# PannelInterface.net
KiCad netlist of a schematic drawn in EAGLE
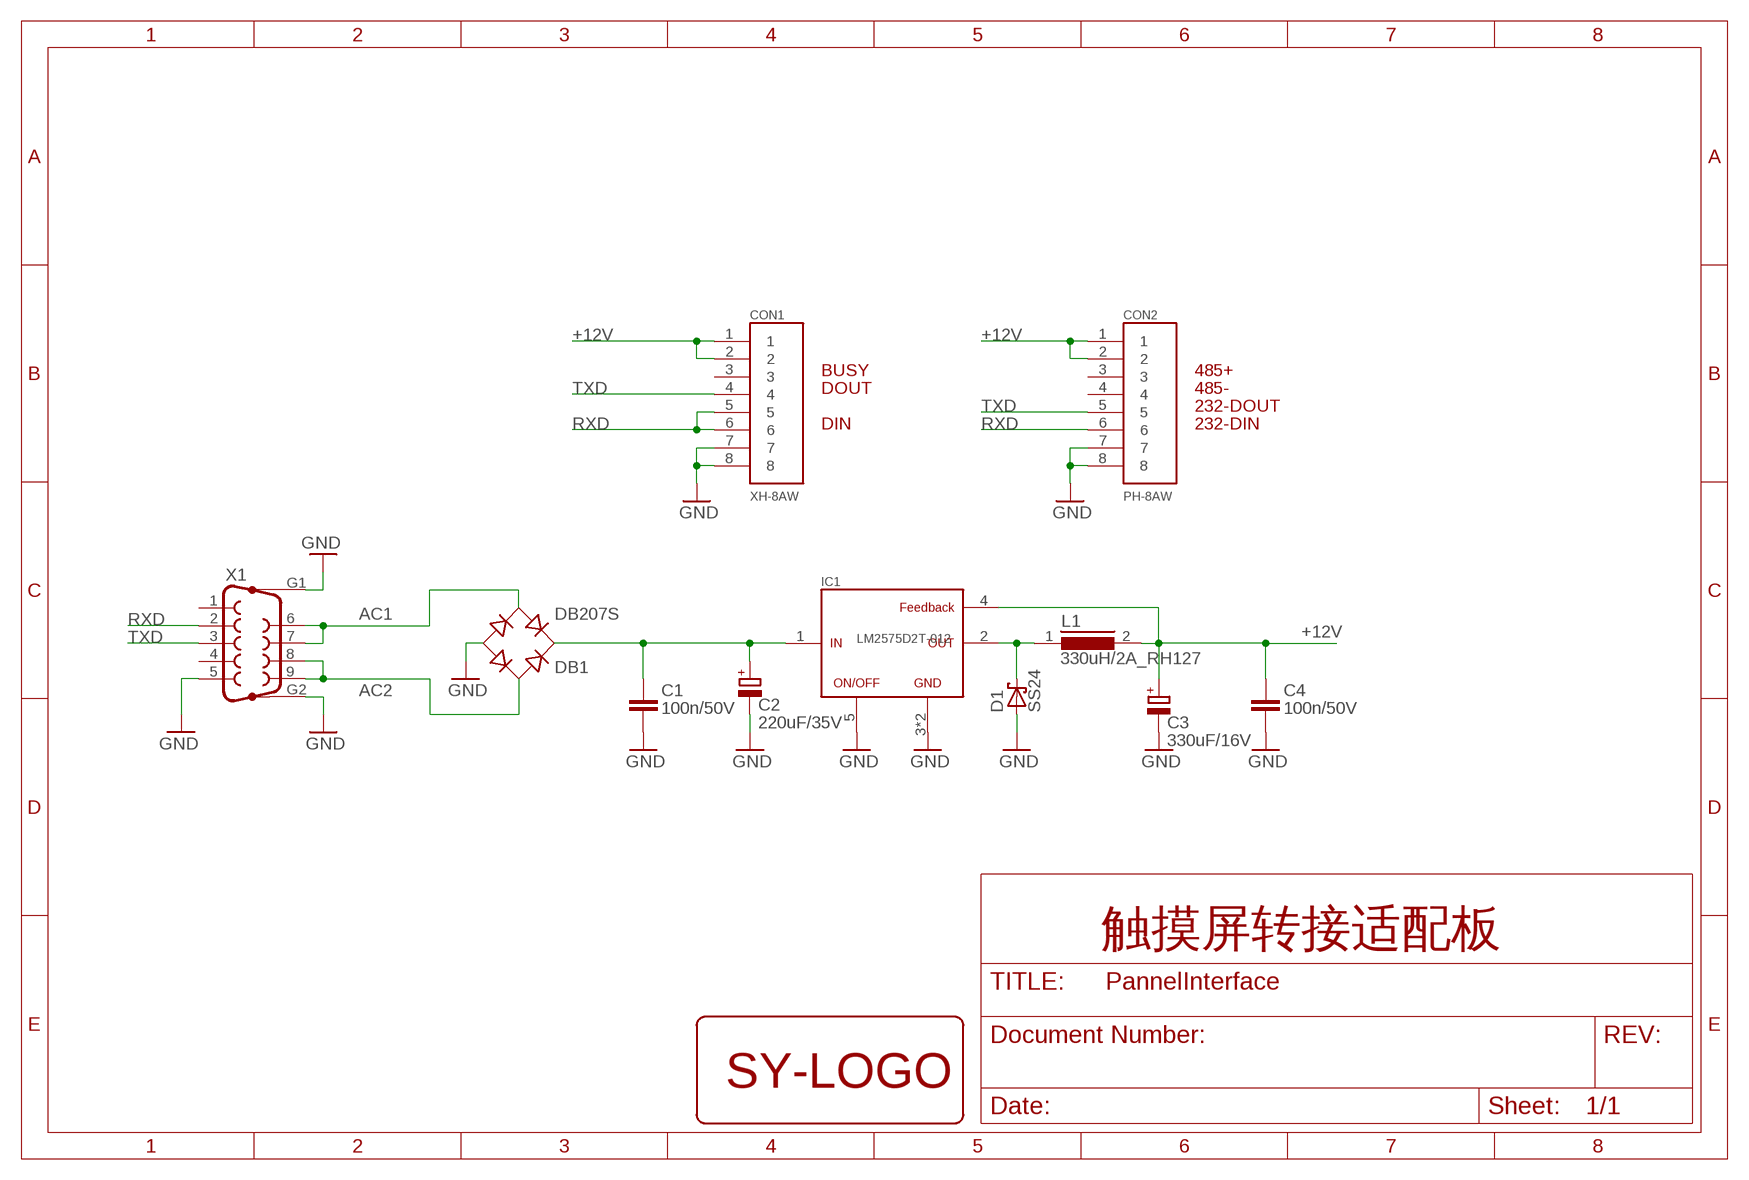
[diagram p0: schematic, sheet 1]

(export (version "E")
  (design (tool "Eeschema 10.0.6"))
  (components
    (comp (ref "C1")
      (value "100n/50V")
      (footprint "eagle-import:C0805")
      (libsource (lib "eagle-import") (part "C0805"))
    )
    (comp (ref "C2")
      (value "220uF/35V")
      (footprint "eagle-import:TT5D11")
      (libsource (lib "eagle-import") (part "CPOL-EUTT5D11"))
    )
    (comp (ref "C3")
      (value "330uF/16V")
      (footprint "eagle-import:UD-8X10_NICHICON")
      (libsource (lib "eagle-import") (part "CPOL-EUUD-8X10"))
    )
    (comp (ref "C4")
      (value "100n/50V")
      (footprint "eagle-import:C0805")
      (libsource (lib "eagle-import") (part "C0805"))
    )
    (comp (ref "CON1")
      (value "XH-8AW")
      (footprint "eagle-import:XH-8AW")
      (libsource (lib "eagle-import") (part "XH-8AW"))
    )
    (comp (ref "CON2")
      (value "PH-8AW")
      (footprint "eagle-import:PH-8AW")
      (libsource (lib "eagle-import") (part "PH-8AW"))
    )
    (comp (ref "D1")
      (value "SS24")
      (footprint "eagle-import:DO214AA")
      (libsource (lib "eagle-import") (part "SCHOTTKY-DIODE-SS24"))
    )
    (comp (ref "DB1")
      (value "DB207S")
      (footprint "eagle-import:DBS")
      (libsource (lib "eagle-import") (part "DB207S"))
    )
    (comp (ref "IC1")
      (value "LM2575D2T-012")
      (footprint "eagle-import:DDPAK-5_MICROCHIP")
      (libsource (lib "eagle-import") (part "LM2575D2T"))
    )
    (comp (ref "L1")
      (value "330uH/2A_RH127")
      (footprint "eagle-import:MSS1260")
      (libsource (lib "eagle-import") (part "POWER_INDUCTOR-1260"))
    )
    (comp (ref "LOGO1")
      (value "SY-LOGO_BOTTOM")
      (footprint "eagle-import:SY-LOGO_BOTTOM")
      (libsource (lib "eagle-import") (part "SY-LOGO_BOTTOM"))
    )
    (comp (ref "X1")
      (value "F09HP")
      (footprint "eagle-import:F09HP")
      (libsource (lib "eagle-import") (part "F09HP"))
    )
  )
  (nets
    (net (code "1") (name "/+12V") (class "Default")
      (node (ref "C3") (pin "+") (pinfunction "+_+") (pintype "passive"))
      (node (ref "C4") (pin "1") (pinfunction "1_1") (pintype "passive"))
      (node (ref "CON1") (pin "1") (pinfunction "1_1") (pintype "passive"))
      (node (ref "CON1") (pin "2") (pinfunction "2_2") (pintype "passive"))
      (node (ref "CON2") (pin "1") (pinfunction "1_1") (pintype "passive"))
      (node (ref "CON2") (pin "2") (pinfunction "2_2") (pintype "passive"))
      (node (ref "IC1") (pin "4") (pinfunction "4_4") (pintype "input"))
      (node (ref "L1") (pin "2") (pinfunction "2_2") (pintype "passive"))
    )
    (net (code "2") (name "/AC1") (class "Default")
      (node (ref "DB1") (pin "AC2") (pinfunction "AC2_AC2") (pintype "passive"))
      (node (ref "X1") (pin "6") (pinfunction "6_6") (pintype "passive"))
      (node (ref "X1") (pin "7") (pinfunction "7_7") (pintype "passive"))
    )
    (net (code "3") (name "/AC2") (class "Default")
      (node (ref "DB1") (pin "AC1") (pinfunction "AC1_AC1") (pintype "passive"))
      (node (ref "X1") (pin "8") (pinfunction "8_8") (pintype "passive"))
      (node (ref "X1") (pin "9") (pinfunction "9_9") (pintype "passive"))
    )
    (net (code "4") (name "/RXD") (class "Default")
      (node (ref "CON1") (pin "5") (pinfunction "5_5") (pintype "passive"))
      (node (ref "CON1") (pin "6") (pinfunction "6_6") (pintype "passive"))
      (node (ref "CON2") (pin "6") (pinfunction "6_6") (pintype "passive"))
      (node (ref "X1") (pin "2") (pinfunction "2_2") (pintype "passive"))
    )
    (net (code "5") (name "/TXD") (class "Default")
      (node (ref "CON1") (pin "4") (pinfunction "4_4") (pintype "passive"))
      (node (ref "CON2") (pin "5") (pinfunction "5_5") (pintype "passive"))
      (node (ref "X1") (pin "3") (pinfunction "3_3") (pintype "passive"))
    )
    (net (code "6") (name "GND") (class "Default")
      (node (ref "C1") (pin "2") (pinfunction "2_2") (pintype "passive"))
      (node (ref "C2") (pin "-") (pinfunction "-_-") (pintype "passive"))
      (node (ref "C3") (pin "-") (pinfunction "-_-") (pintype "passive"))
      (node (ref "C4") (pin "2") (pinfunction "2_2") (pintype "passive"))
      (node (ref "CON1") (pin "7") (pinfunction "7_7") (pintype "passive"))
      (node (ref "CON1") (pin "8") (pinfunction "8_8") (pintype "passive"))
      (node (ref "CON2") (pin "7") (pinfunction "7_7") (pintype "passive"))
      (node (ref "CON2") (pin "8") (pinfunction "8_8") (pintype "passive"))
      (node (ref "D1") (pin "A") (pinfunction "A_A") (pintype "passive"))
      (node (ref "DB1") (pin "-") (pinfunction "-_-") (pintype "passive"))
      (node (ref "IC1") (pin "3") (pinfunction "3_3") (pintype "power_in"))
      (node (ref "IC1") (pin "5") (pinfunction "5_5") (pintype "input"))
      (node (ref "IC1") (pin "6") (pinfunction "3_6") (pintype "power_in"))
      (node (ref "X1") (pin "5") (pinfunction "5_5") (pintype "passive"))
      (node (ref "X1") (pin "G1") (pinfunction "G1_G1") (pintype "passive"))
      (node (ref "X1") (pin "G2") (pinfunction "G2_G2") (pintype "passive"))
    )
    (net (code "7") (name "Net-(C1-Pad1)") (class "Default")
      (node (ref "C1") (pin "1") (pinfunction "1_1") (pintype "passive"))
      (node (ref "C2") (pin "+") (pinfunction "+_+") (pintype "passive"))
      (node (ref "DB1") (pin "+") (pinfunction "+_+") (pintype "passive"))
      (node (ref "IC1") (pin "1") (pinfunction "1_1") (pintype "input"))
    )
    (net (code "8") (name "Net-(D1-PadC)") (class "Default")
      (node (ref "D1") (pin "C") (pinfunction "C_C") (pintype "passive"))
      (node (ref "IC1") (pin "2") (pinfunction "2_2") (pintype "output"))
      (node (ref "L1") (pin "1") (pinfunction "1_1") (pintype "passive"))
    )
    (net (code "9") (name "unconnected-(CON1-Pad3)") (class "Default")
      (node (ref "CON1") (pin "3") (pinfunction "3_3") (pintype "passive"))
    )
    (net (code "10") (name "unconnected-(CON2-Pad3)") (class "Default")
      (node (ref "CON2") (pin "3") (pinfunction "3_3") (pintype "passive"))
    )
    (net (code "11") (name "unconnected-(CON2-Pad4)") (class "Default")
      (node (ref "CON2") (pin "4") (pinfunction "4_4") (pintype "passive"))
    )
    (net (code "12") (name "unconnected-(X1-Pad1)") (class "Default")
      (node (ref "X1") (pin "1") (pinfunction "1_1") (pintype "passive"))
    )
    (net (code "13") (name "unconnected-(X1-Pad4)") (class "Default")
      (node (ref "X1") (pin "4") (pinfunction "4_4") (pintype "passive"))
    )
  )
)
